# PhaseDetector.net
KiCad netlist of a schematic drawn in Altium Designer
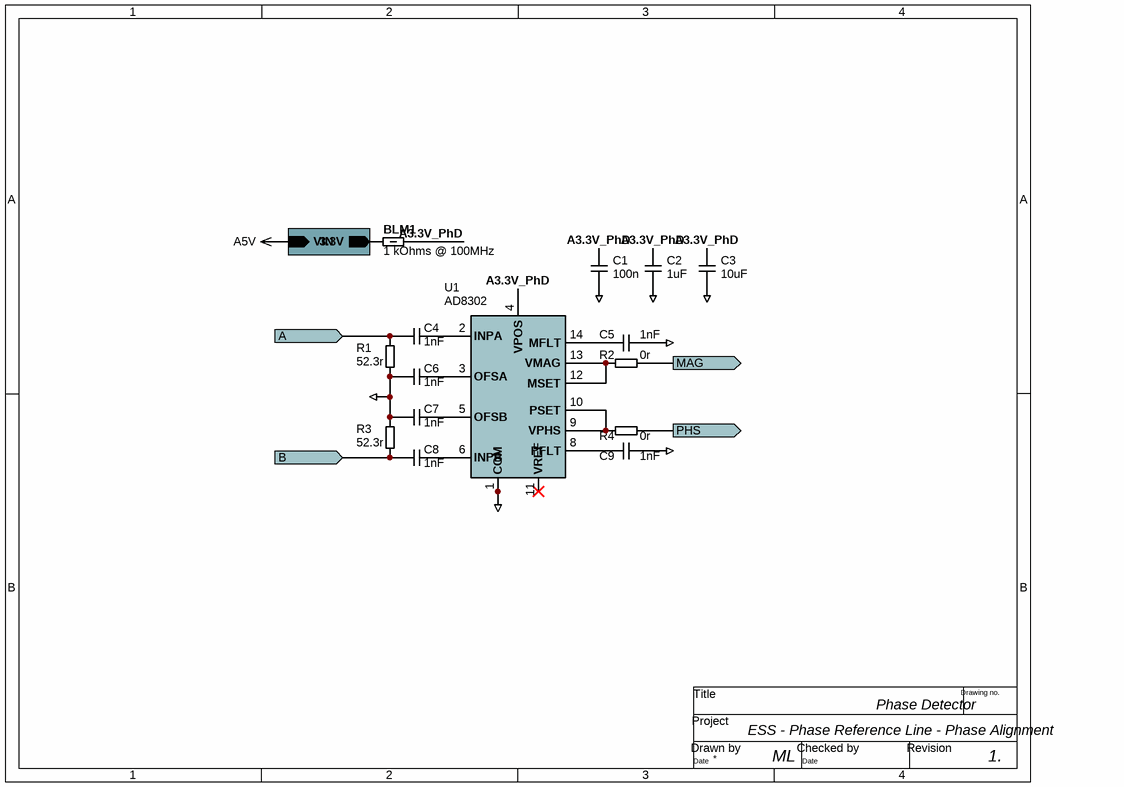
[diagram p0: PhaseDetector.SchDoc]

(export (version "E")
  (design (tool "Eeschema 10.0.6"))
  (components
    (comp (ref "BLM1")
      (value "1 kOhms @ 100MHz")
      (footprint "0402-Inductor")
      (description "1 kOhms @ 100MHz 1 Signal Line Ferrite Bead 0402 (1005 Metric) 300mA 650mOhm")
      (libsource (lib "PRL_PDC") (part "BLM15AG102SZ1D"))
    )
    (comp (ref "C1")
      (value "100n")
      (footprint "0402-Capacitor")
      (description "Capacitor 0402")
      (fields (field (name "TOLERANCE") "±20%"))
      (libsource (lib "PRL_PDC") (part "C_0402"))
    )
    (comp (ref "C2")
      (value "1uF")
      (footprint "0603-Capacitor")
      (description "Capacitor 0603")
      (fields (field (name "TOLERANCE") "±20%"))
      (libsource (lib "PRL_PDC") (part "C_0603"))
    )
    (comp (ref "C3")
      (value "10uF")
      (footprint "1206-capacitor")
      (description "Capacitor 1206")
      (fields (field (name "TOLERANCE") "±20%"))
      (libsource (lib "PRL_PDC") (part "C_1206"))
    )
    (comp (ref "C4")
      (value "1nF")
      (footprint "0603-Capacitor")
      (description "Capacitor 0603")
      (fields (field (name "TOLERANCE") "±20%"))
      (libsource (lib "PRL_PDC") (part "C_0603"))
    )
    (comp (ref "C5")
      (value "1nF")
      (footprint "0603-Capacitor")
      (description "Capacitor 0603")
      (fields (field (name "TOLERANCE") "±20%"))
      (libsource (lib "PRL_PDC") (part "C_0603"))
    )
    (comp (ref "C6")
      (value "1nF")
      (footprint "0603-Capacitor")
      (description "Capacitor 0603")
      (fields (field (name "TOLERANCE") "±20%"))
      (libsource (lib "PRL_PDC") (part "C_0603"))
    )
    (comp (ref "C7")
      (value "1nF")
      (footprint "0603-Capacitor")
      (description "Capacitor 0603")
      (fields (field (name "TOLERANCE") "±20%"))
      (libsource (lib "PRL_PDC") (part "C_0603"))
    )
    (comp (ref "C8")
      (value "1nF")
      (footprint "0603-Capacitor")
      (description "Capacitor 0603")
      (fields (field (name "TOLERANCE") "±20%"))
      (libsource (lib "PRL_PDC") (part "C_0603"))
    )
    (comp (ref "C9")
      (value "1nF")
      (footprint "0603-Capacitor")
      (description "Capacitor 0603")
      (fields (field (name "TOLERANCE") "±20%"))
      (libsource (lib "PRL_PDC") (part "C_0603"))
    )
    (comp (ref "R1")
      (value "52.3r")
      (footprint "0603-RESISTOR")
      (description "Resistor 0603")
      (fields (field (name "TOLERANCE") "±1%"))
      (libsource (lib "") (part "R_0603_1"))
    )
    (comp (ref "R2")
      (value "0r")
      (footprint "0603-RESISTOR")
      (description "Resistor 0603")
      (fields (field (name "TOLERANCE") "±1%"))
      (libsource (lib "PRL_PDC") (part "R_0603"))
    )
    (comp (ref "R3")
      (value "52.3r")
      (footprint "0603-RESISTOR")
      (description "Resistor 0603")
      (fields (field (name "TOLERANCE") "±1%"))
      (libsource (lib "") (part "R_0603_1"))
    )
    (comp (ref "R4")
      (value "0r")
      (footprint "0603-RESISTOR")
      (description "Resistor 0603")
      (fields (field (name "TOLERANCE") "±1%"))
      (libsource (lib "PRL_PDC") (part "R_0603"))
    )
    (comp (ref "U1")
      (value "AD8302")
      (footprint "TSSOP14")
      (description "RF/IF Gain and Phase Detector\r\n• LF–2.7 GHz")
      (libsource (lib "PRL_PDC") (part "AD8302"))
    )
  )
  (nets
    (net (code "1") (name "/3.3V") (class "Default") (node (ref "BLM1") (pin "1") (pintype "passive")))
    (net (code "2") (name "/A") (class "Default")
      (node (ref "C4") (pin "1") (pinfunction "1_1") (pintype "passive"))
      (node (ref "R1") (pin "2") (pinfunction "2_2") (pintype "passive"))
    )
    (net (code "3") (name "/A3.3V_PhD") (class "Default")
      (node (ref "BLM1") (pin "2") (pintype "passive"))
      (node (ref "C1") (pin "2") (pinfunction "2_2") (pintype "passive"))
      (node (ref "C2") (pin "2") (pinfunction "2_2") (pintype "passive"))
      (node (ref "C3") (pin "2") (pinfunction "2_2") (pintype "passive"))
      (node (ref "U1") (pin "4") (pinfunction "VPOS_4") (pintype "passive"))
    )
    (net (code "4") (name "/B") (class "Default")
      (node (ref "C8") (pin "1") (pinfunction "1_1") (pintype "passive"))
      (node (ref "R3") (pin "1") (pinfunction "1_1") (pintype "passive"))
    )
    (net (code "5") (name "/MAG") (class "Default")
      (node (ref "R2") (pin "1") (pinfunction "1_1") (pintype "passive"))
    )
    (net (code "6") (name "/PHS") (class "Default")
      (node (ref "R4") (pin "1") (pinfunction "1_1") (pintype "passive"))
    )
    (net (code "8") (name "GND") (class "Default")
      (node (ref "C1") (pin "1") (pinfunction "1_1") (pintype "passive"))
      (node (ref "C2") (pin "1") (pinfunction "1_1") (pintype "passive"))
      (node (ref "C3") (pin "1") (pinfunction "1_1") (pintype "passive"))
      (node (ref "C5") (pin "2") (pinfunction "2_2") (pintype "passive"))
      (node (ref "C6") (pin "1") (pinfunction "1_1") (pintype "passive"))
      (node (ref "C7") (pin "1") (pinfunction "1_1") (pintype "passive"))
      (node (ref "C9") (pin "2") (pinfunction "2_2") (pintype "passive"))
      (node (ref "R1") (pin "1") (pinfunction "1_1") (pintype "passive"))
      (node (ref "R3") (pin "2") (pinfunction "2_2") (pintype "passive"))
      (node (ref "U1") (pin "1") (pinfunction "COM_1") (pintype "passive"))
      (node (ref "U1") (pin "7") (pinfunction "COM_7") (pintype "passive"))
    )
    (net (code "9") (name "Net-(U1-INPA)") (class "Default")
      (node (ref "C4") (pin "2") (pinfunction "2_2") (pintype "passive"))
      (node (ref "U1") (pin "2") (pinfunction "INPA_2") (pintype "passive"))
    )
    (net (code "10") (name "Net-(U1-INPB)") (class "Default")
      (node (ref "C8") (pin "2") (pinfunction "2_2") (pintype "passive"))
      (node (ref "U1") (pin "6") (pinfunction "INPB_6") (pintype "passive"))
    )
    (net (code "11") (name "Net-(U1-MFLT)") (class "Default")
      (node (ref "C5") (pin "1") (pinfunction "1_1") (pintype "passive"))
      (node (ref "U1") (pin "14") (pinfunction "MFLT_14") (pintype "passive"))
    )
    (net (code "12") (name "Net-(U1-MSET)") (class "Default")
      (node (ref "R2") (pin "2") (pinfunction "2_2") (pintype "passive"))
      (node (ref "U1") (pin "12") (pinfunction "MSET_12") (pintype "passive"))
      (node (ref "U1") (pin "13") (pinfunction "VMAG_13") (pintype "passive"))
    )
    (net (code "13") (name "Net-(U1-OFSA)") (class "Default")
      (node (ref "C6") (pin "2") (pinfunction "2_2") (pintype "passive"))
      (node (ref "U1") (pin "3") (pinfunction "OFSA_3") (pintype "passive"))
    )
    (net (code "14") (name "Net-(U1-OFSB)") (class "Default")
      (node (ref "C7") (pin "2") (pinfunction "2_2") (pintype "passive"))
      (node (ref "U1") (pin "5") (pinfunction "OFSB_5") (pintype "passive"))
    )
    (net (code "15") (name "Net-(U1-PFLT)") (class "Default")
      (node (ref "C9") (pin "1") (pinfunction "1_1") (pintype "passive"))
      (node (ref "U1") (pin "8") (pinfunction "PFLT_8") (pintype "passive"))
    )
    (net (code "16") (name "Net-(U1-PSET)") (class "Default")
      (node (ref "R4") (pin "2") (pinfunction "2_2") (pintype "passive"))
      (node (ref "U1") (pin "10") (pinfunction "PSET_10") (pintype "passive"))
      (node (ref "U1") (pin "9") (pinfunction "VPHS_9") (pintype "passive"))
    )
    (net (code "17") (name "unconnected-(U1-VREF-Pad11)") (class "Default")
      (node (ref "U1") (pin "11") (pinfunction "VREF_11") (pintype "passive+no_connect"))
    )
  )
)
